# headers.net
KiCad netlist of a schematic drawn in Altium Designer
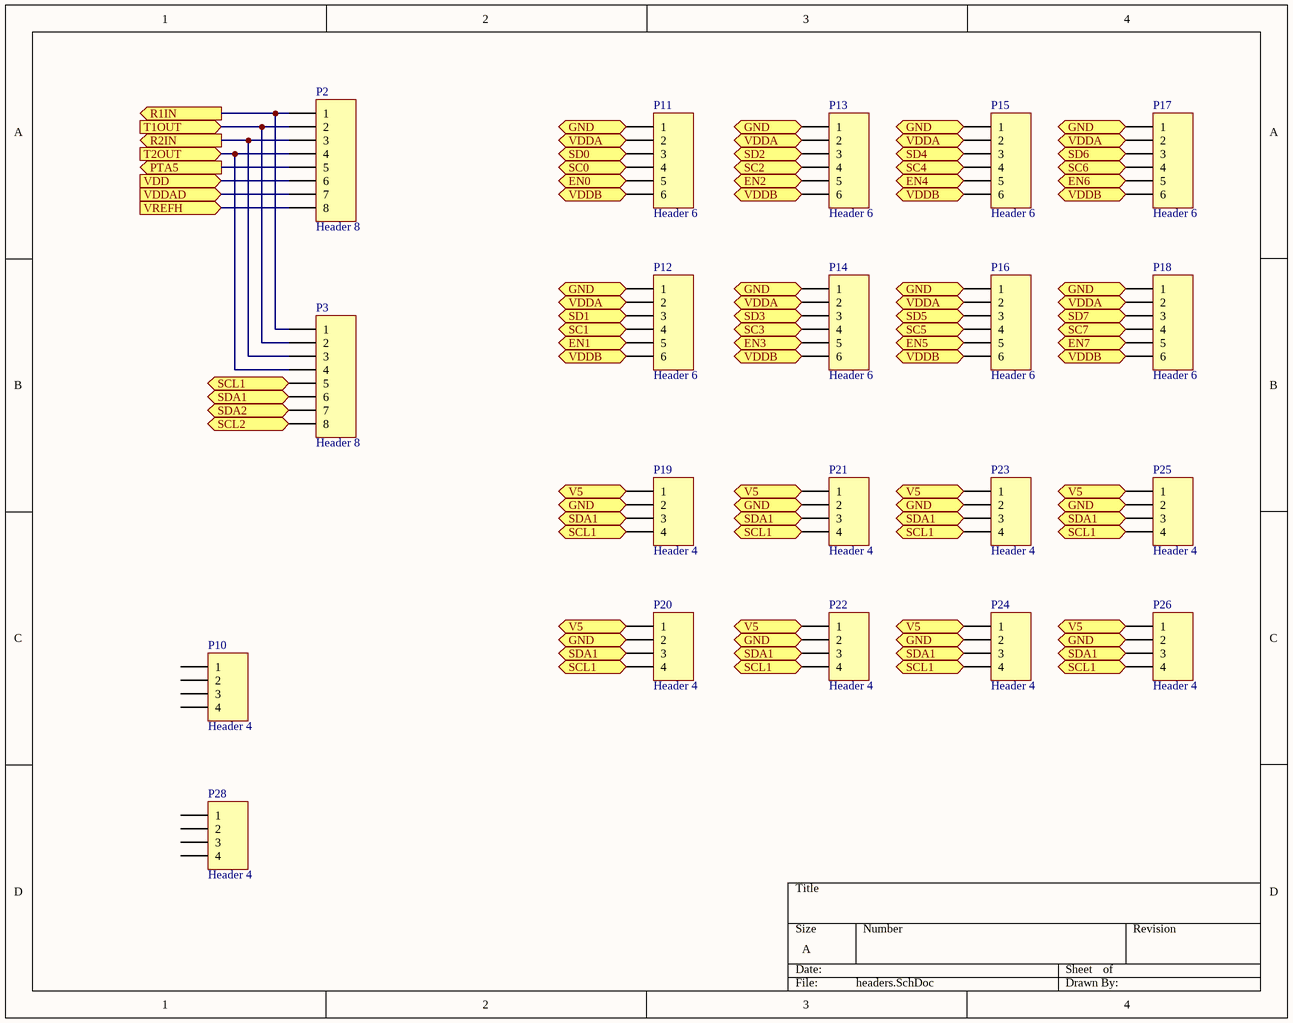
[diagram p0: headers.SchDoc]

(export (version "E")
  (design (tool "Eeschema 10.0.6"))
  (components
    (comp (ref "P2")
      (value "Header 8")
      (footprint "HDR1X8")
      (description "Header, 8-Pin")
      (fields (field (name "PUBLISHER") "Altium Limited"))
      (libsource (lib "Miscellaneous Connectors") (part "Header 8"))
    )
    (comp (ref "P3")
      (value "Header 8")
      (footprint "HDR1X8")
      (description "Header, 8-Pin")
      (fields (field (name "PUBLISHER") "Altium Limited"))
      (libsource (lib "Miscellaneous Connectors") (part "Header 8"))
    )
    (comp (ref "P10")
      (value "Header 4")
      (footprint "HDR1X4")
      (description "Header, 4-Pin")
      (fields (field (name "PUBLISHER") "Altium Limited"))
      (libsource (lib "Miscellaneous Connectors") (part "Header 4"))
    )
    (comp (ref "P11")
      (value "Header 6")
      (footprint "HDR1X6")
      (description "Header, 6-Pin")
      (fields (field (name "PUBLISHER") "Altium Limited"))
      (libsource (lib "Miscellaneous Connectors") (part "Header 6"))
    )
    (comp (ref "P12")
      (value "Header 6")
      (footprint "HDR1X6")
      (description "Header, 6-Pin")
      (fields (field (name "PUBLISHER") "Altium Limited"))
      (libsource (lib "Miscellaneous Connectors") (part "Header 6"))
    )
    (comp (ref "P13")
      (value "Header 6")
      (footprint "HDR1X6")
      (description "Header, 6-Pin")
      (fields (field (name "PUBLISHER") "Altium Limited"))
      (libsource (lib "Miscellaneous Connectors") (part "Header 6"))
    )
    (comp (ref "P14")
      (value "Header 6")
      (footprint "HDR1X6")
      (description "Header, 6-Pin")
      (fields (field (name "PUBLISHER") "Altium Limited"))
      (libsource (lib "Miscellaneous Connectors") (part "Header 6"))
    )
    (comp (ref "P15")
      (value "Header 6")
      (footprint "HDR1X6")
      (description "Header, 6-Pin")
      (fields (field (name "PUBLISHER") "Altium Limited"))
      (libsource (lib "Miscellaneous Connectors") (part "Header 6"))
    )
    (comp (ref "P16")
      (value "Header 6")
      (footprint "HDR1X6")
      (description "Header, 6-Pin")
      (fields (field (name "PUBLISHER") "Altium Limited"))
      (libsource (lib "Miscellaneous Connectors") (part "Header 6"))
    )
    (comp (ref "P17")
      (value "Header 6")
      (footprint "HDR1X6")
      (description "Header, 6-Pin")
      (fields (field (name "PUBLISHER") "Altium Limited"))
      (libsource (lib "Miscellaneous Connectors") (part "Header 6"))
    )
    (comp (ref "P18")
      (value "Header 6")
      (footprint "HDR1X6")
      (description "Header, 6-Pin")
      (fields (field (name "PUBLISHER") "Altium Limited"))
      (libsource (lib "Miscellaneous Connectors") (part "Header 6"))
    )
    (comp (ref "P19")
      (value "Header 4")
      (footprint "HDR1X4")
      (description "Header, 4-Pin")
      (fields (field (name "PUBLISHER") "Altium Limited"))
      (libsource (lib "Miscellaneous Connectors") (part "Header 4"))
    )
    (comp (ref "P20")
      (value "Header 4")
      (footprint "HDR1X4")
      (description "Header, 4-Pin")
      (fields (field (name "PUBLISHER") "Altium Limited"))
      (libsource (lib "Miscellaneous Connectors") (part "Header 4"))
    )
    (comp (ref "P21")
      (value "Header 4")
      (footprint "HDR1X4")
      (description "Header, 4-Pin")
      (fields (field (name "PUBLISHER") "Altium Limited"))
      (libsource (lib "Miscellaneous Connectors") (part "Header 4"))
    )
    (comp (ref "P22")
      (value "Header 4")
      (footprint "HDR1X4")
      (description "Header, 4-Pin")
      (fields (field (name "PUBLISHER") "Altium Limited"))
      (libsource (lib "Miscellaneous Connectors") (part "Header 4"))
    )
    (comp (ref "P23")
      (value "Header 4")
      (footprint "HDR1X4")
      (description "Header, 4-Pin")
      (fields (field (name "PUBLISHER") "Altium Limited"))
      (libsource (lib "Miscellaneous Connectors") (part "Header 4"))
    )
    (comp (ref "P24")
      (value "Header 4")
      (footprint "HDR1X4")
      (description "Header, 4-Pin")
      (fields (field (name "PUBLISHER") "Altium Limited"))
      (libsource (lib "Miscellaneous Connectors") (part "Header 4"))
    )
    (comp (ref "P25")
      (value "Header 4")
      (footprint "HDR1X4")
      (description "Header, 4-Pin")
      (fields (field (name "PUBLISHER") "Altium Limited"))
      (libsource (lib "Miscellaneous Connectors") (part "Header 4"))
    )
    (comp (ref "P26")
      (value "Header 4")
      (footprint "HDR1X4")
      (description "Header, 4-Pin")
      (fields (field (name "PUBLISHER") "Altium Limited"))
      (libsource (lib "Miscellaneous Connectors") (part "Header 4"))
    )
    (comp (ref "P28")
      (value "Header 4")
      (footprint "HDR1X4")
      (description "Header, 4-Pin")
      (fields (field (name "PUBLISHER") "Altium Limited"))
      (libsource (lib "Miscellaneous Connectors") (part "Header 4"))
    )
  )
  (nets
    (net (code "1") (name "/EN0") (class "Default")
      (node (ref "P11") (pin "5") (pinfunction "5_5") (pintype "passive"))
    )
    (net (code "2") (name "/EN1") (class "Default")
      (node (ref "P12") (pin "5") (pinfunction "5_5") (pintype "passive"))
    )
    (net (code "3") (name "/EN2") (class "Default")
      (node (ref "P13") (pin "5") (pinfunction "5_5") (pintype "passive"))
    )
    (net (code "4") (name "/EN3") (class "Default")
      (node (ref "P14") (pin "5") (pinfunction "5_5") (pintype "passive"))
    )
    (net (code "5") (name "/EN4") (class "Default")
      (node (ref "P15") (pin "5") (pinfunction "5_5") (pintype "passive"))
    )
    (net (code "6") (name "/EN5") (class "Default")
      (node (ref "P16") (pin "5") (pinfunction "5_5") (pintype "passive"))
    )
    (net (code "7") (name "/EN6") (class "Default")
      (node (ref "P17") (pin "5") (pinfunction "5_5") (pintype "passive"))
    )
    (net (code "8") (name "/EN7") (class "Default")
      (node (ref "P18") (pin "5") (pinfunction "5_5") (pintype "passive"))
    )
    (net (code "9") (name "/GND") (class "Default")
      (node (ref "P11") (pin "1") (pinfunction "1_1") (pintype "passive"))
      (node (ref "P12") (pin "1") (pinfunction "1_1") (pintype "passive"))
      (node (ref "P13") (pin "1") (pinfunction "1_1") (pintype "passive"))
      (node (ref "P14") (pin "1") (pinfunction "1_1") (pintype "passive"))
      (node (ref "P15") (pin "1") (pinfunction "1_1") (pintype "passive"))
      (node (ref "P16") (pin "1") (pinfunction "1_1") (pintype "passive"))
      (node (ref "P17") (pin "1") (pinfunction "1_1") (pintype "passive"))
      (node (ref "P18") (pin "1") (pinfunction "1_1") (pintype "passive"))
      (node (ref "P19") (pin "2") (pinfunction "2_2") (pintype "passive"))
      (node (ref "P20") (pin "2") (pinfunction "2_2") (pintype "passive"))
      (node (ref "P21") (pin "2") (pinfunction "2_2") (pintype "passive"))
      (node (ref "P22") (pin "2") (pinfunction "2_2") (pintype "passive"))
      (node (ref "P23") (pin "2") (pinfunction "2_2") (pintype "passive"))
      (node (ref "P24") (pin "2") (pinfunction "2_2") (pintype "passive"))
      (node (ref "P25") (pin "2") (pinfunction "2_2") (pintype "passive"))
      (node (ref "P26") (pin "2") (pinfunction "2_2") (pintype "passive"))
    )
    (net (code "10") (name "/PTA5") (class "Default")
      (node (ref "P2") (pin "5") (pinfunction "5_5") (pintype "passive"))
    )
    (net (code "11") (name "/R1IN") (class "Default")
      (node (ref "P2") (pin "1") (pinfunction "1_1") (pintype "passive"))
      (node (ref "P3") (pin "1") (pinfunction "1_1") (pintype "passive"))
    )
    (net (code "12") (name "/R2IN") (class "Default")
      (node (ref "P2") (pin "3") (pinfunction "3_3") (pintype "passive"))
      (node (ref "P3") (pin "3") (pinfunction "3_3") (pintype "passive"))
    )
    (net (code "13") (name "/SC0") (class "Default")
      (node (ref "P11") (pin "4") (pinfunction "4_4") (pintype "passive"))
    )
    (net (code "14") (name "/SC1") (class "Default")
      (node (ref "P12") (pin "4") (pinfunction "4_4") (pintype "passive"))
    )
    (net (code "15") (name "/SC2") (class "Default")
      (node (ref "P13") (pin "4") (pinfunction "4_4") (pintype "passive"))
    )
    (net (code "16") (name "/SC3") (class "Default")
      (node (ref "P14") (pin "4") (pinfunction "4_4") (pintype "passive"))
    )
    (net (code "17") (name "/SC4") (class "Default")
      (node (ref "P15") (pin "4") (pinfunction "4_4") (pintype "passive"))
    )
    (net (code "18") (name "/SC5") (class "Default")
      (node (ref "P16") (pin "4") (pinfunction "4_4") (pintype "passive"))
    )
    (net (code "19") (name "/SC6") (class "Default")
      (node (ref "P17") (pin "4") (pinfunction "4_4") (pintype "passive"))
    )
    (net (code "20") (name "/SC7") (class "Default")
      (node (ref "P18") (pin "4") (pinfunction "4_4") (pintype "passive"))
    )
    (net (code "21") (name "/SCL1") (class "Default")
      (node (ref "P19") (pin "4") (pinfunction "4_4") (pintype "passive"))
      (node (ref "P20") (pin "4") (pinfunction "4_4") (pintype "passive"))
      (node (ref "P21") (pin "4") (pinfunction "4_4") (pintype "passive"))
      (node (ref "P22") (pin "4") (pinfunction "4_4") (pintype "passive"))
      (node (ref "P23") (pin "4") (pinfunction "4_4") (pintype "passive"))
      (node (ref "P24") (pin "4") (pinfunction "4_4") (pintype "passive"))
      (node (ref "P25") (pin "4") (pinfunction "4_4") (pintype "passive"))
      (node (ref "P26") (pin "4") (pinfunction "4_4") (pintype "passive"))
      (node (ref "P3") (pin "5") (pinfunction "5_5") (pintype "passive"))
    )
    (net (code "22") (name "/SCL2") (class "Default")
      (node (ref "P3") (pin "8") (pinfunction "8_8") (pintype "passive"))
    )
    (net (code "23") (name "/SD0") (class "Default")
      (node (ref "P11") (pin "3") (pinfunction "3_3") (pintype "passive"))
    )
    (net (code "24") (name "/SD1") (class "Default")
      (node (ref "P12") (pin "3") (pinfunction "3_3") (pintype "passive"))
    )
    (net (code "25") (name "/SD2") (class "Default")
      (node (ref "P13") (pin "3") (pinfunction "3_3") (pintype "passive"))
    )
    (net (code "26") (name "/SD3") (class "Default")
      (node (ref "P14") (pin "3") (pinfunction "3_3") (pintype "passive"))
    )
    (net (code "27") (name "/SD4") (class "Default")
      (node (ref "P15") (pin "3") (pinfunction "3_3") (pintype "passive"))
    )
    (net (code "28") (name "/SD5") (class "Default")
      (node (ref "P16") (pin "3") (pinfunction "3_3") (pintype "passive"))
    )
    (net (code "29") (name "/SD6") (class "Default")
      (node (ref "P17") (pin "3") (pinfunction "3_3") (pintype "passive"))
    )
    (net (code "30") (name "/SD7") (class "Default")
      (node (ref "P18") (pin "3") (pinfunction "3_3") (pintype "passive"))
    )
    (net (code "31") (name "/SDA1") (class "Default")
      (node (ref "P19") (pin "3") (pinfunction "3_3") (pintype "passive"))
      (node (ref "P20") (pin "3") (pinfunction "3_3") (pintype "passive"))
      (node (ref "P21") (pin "3") (pinfunction "3_3") (pintype "passive"))
      (node (ref "P22") (pin "3") (pinfunction "3_3") (pintype "passive"))
      (node (ref "P23") (pin "3") (pinfunction "3_3") (pintype "passive"))
      (node (ref "P24") (pin "3") (pinfunction "3_3") (pintype "passive"))
      (node (ref "P25") (pin "3") (pinfunction "3_3") (pintype "passive"))
      (node (ref "P26") (pin "3") (pinfunction "3_3") (pintype "passive"))
      (node (ref "P3") (pin "6") (pinfunction "6_6") (pintype "passive"))
    )
    (net (code "32") (name "/SDA2") (class "Default")
      (node (ref "P3") (pin "7") (pinfunction "7_7") (pintype "passive"))
    )
    (net (code "33") (name "/T1OUT") (class "Default")
      (node (ref "P2") (pin "2") (pinfunction "2_2") (pintype "passive"))
      (node (ref "P3") (pin "2") (pinfunction "2_2") (pintype "passive"))
    )
    (net (code "34") (name "/T2OUT") (class "Default")
      (node (ref "P2") (pin "4") (pinfunction "4_4") (pintype "passive"))
      (node (ref "P3") (pin "4") (pinfunction "4_4") (pintype "passive"))
    )
    (net (code "35") (name "/V5") (class "Default")
      (node (ref "P19") (pin "1") (pinfunction "1_1") (pintype "passive"))
      (node (ref "P20") (pin "1") (pinfunction "1_1") (pintype "passive"))
      (node (ref "P21") (pin "1") (pinfunction "1_1") (pintype "passive"))
      (node (ref "P22") (pin "1") (pinfunction "1_1") (pintype "passive"))
      (node (ref "P23") (pin "1") (pinfunction "1_1") (pintype "passive"))
      (node (ref "P24") (pin "1") (pinfunction "1_1") (pintype "passive"))
      (node (ref "P25") (pin "1") (pinfunction "1_1") (pintype "passive"))
      (node (ref "P26") (pin "1") (pinfunction "1_1") (pintype "passive"))
    )
    (net (code "36") (name "/VDD") (class "Default")
      (node (ref "P2") (pin "6") (pinfunction "6_6") (pintype "passive"))
    )
    (net (code "37") (name "/VDDA") (class "Default")
      (node (ref "P11") (pin "2") (pinfunction "2_2") (pintype "passive"))
      (node (ref "P12") (pin "2") (pinfunction "2_2") (pintype "passive"))
      (node (ref "P13") (pin "2") (pinfunction "2_2") (pintype "passive"))
      (node (ref "P14") (pin "2") (pinfunction "2_2") (pintype "passive"))
      (node (ref "P15") (pin "2") (pinfunction "2_2") (pintype "passive"))
      (node (ref "P16") (pin "2") (pinfunction "2_2") (pintype "passive"))
      (node (ref "P17") (pin "2") (pinfunction "2_2") (pintype "passive"))
      (node (ref "P18") (pin "2") (pinfunction "2_2") (pintype "passive"))
    )
    (net (code "38") (name "/VDDAD") (class "Default")
      (node (ref "P2") (pin "7") (pinfunction "7_7") (pintype "passive"))
    )
    (net (code "39") (name "/VDDB") (class "Default")
      (node (ref "P11") (pin "6") (pinfunction "6_6") (pintype "passive"))
      (node (ref "P12") (pin "6") (pinfunction "6_6") (pintype "passive"))
      (node (ref "P13") (pin "6") (pinfunction "6_6") (pintype "passive"))
      (node (ref "P14") (pin "6") (pinfunction "6_6") (pintype "passive"))
      (node (ref "P15") (pin "6") (pinfunction "6_6") (pintype "passive"))
      (node (ref "P16") (pin "6") (pinfunction "6_6") (pintype "passive"))
      (node (ref "P17") (pin "6") (pinfunction "6_6") (pintype "passive"))
      (node (ref "P18") (pin "6") (pinfunction "6_6") (pintype "passive"))
    )
    (net (code "40") (name "/VREFH") (class "Default")
      (node (ref "P2") (pin "8") (pinfunction "8_8") (pintype "passive"))
    )
    (net (code "41") (name "unconnected-(P10-Pad1)") (class "Default")
      (node (ref "P10") (pin "1") (pinfunction "1_1") (pintype "passive"))
    )
    (net (code "42") (name "unconnected-(P10-Pad2)") (class "Default")
      (node (ref "P10") (pin "2") (pinfunction "2_2") (pintype "passive"))
    )
    (net (code "43") (name "unconnected-(P10-Pad3)") (class "Default")
      (node (ref "P10") (pin "3") (pinfunction "3_3") (pintype "passive"))
    )
    (net (code "44") (name "unconnected-(P10-Pad4)") (class "Default")
      (node (ref "P10") (pin "4") (pinfunction "4_4") (pintype "passive"))
    )
    (net (code "45") (name "unconnected-(P28-Pad1)") (class "Default")
      (node (ref "P28") (pin "1") (pinfunction "1_1") (pintype "passive"))
    )
    (net (code "46") (name "unconnected-(P28-Pad2)") (class "Default")
      (node (ref "P28") (pin "2") (pinfunction "2_2") (pintype "passive"))
    )
    (net (code "47") (name "unconnected-(P28-Pad3)") (class "Default")
      (node (ref "P28") (pin "3") (pinfunction "3_3") (pintype "passive"))
    )
    (net (code "48") (name "unconnected-(P28-Pad4)") (class "Default")
      (node (ref "P28") (pin "4") (pinfunction "4_4") (pintype "passive"))
    )
  )
)
